# PERfECT-PRO2.net
KiCad netlist of a schematic drawn in Altium Designer
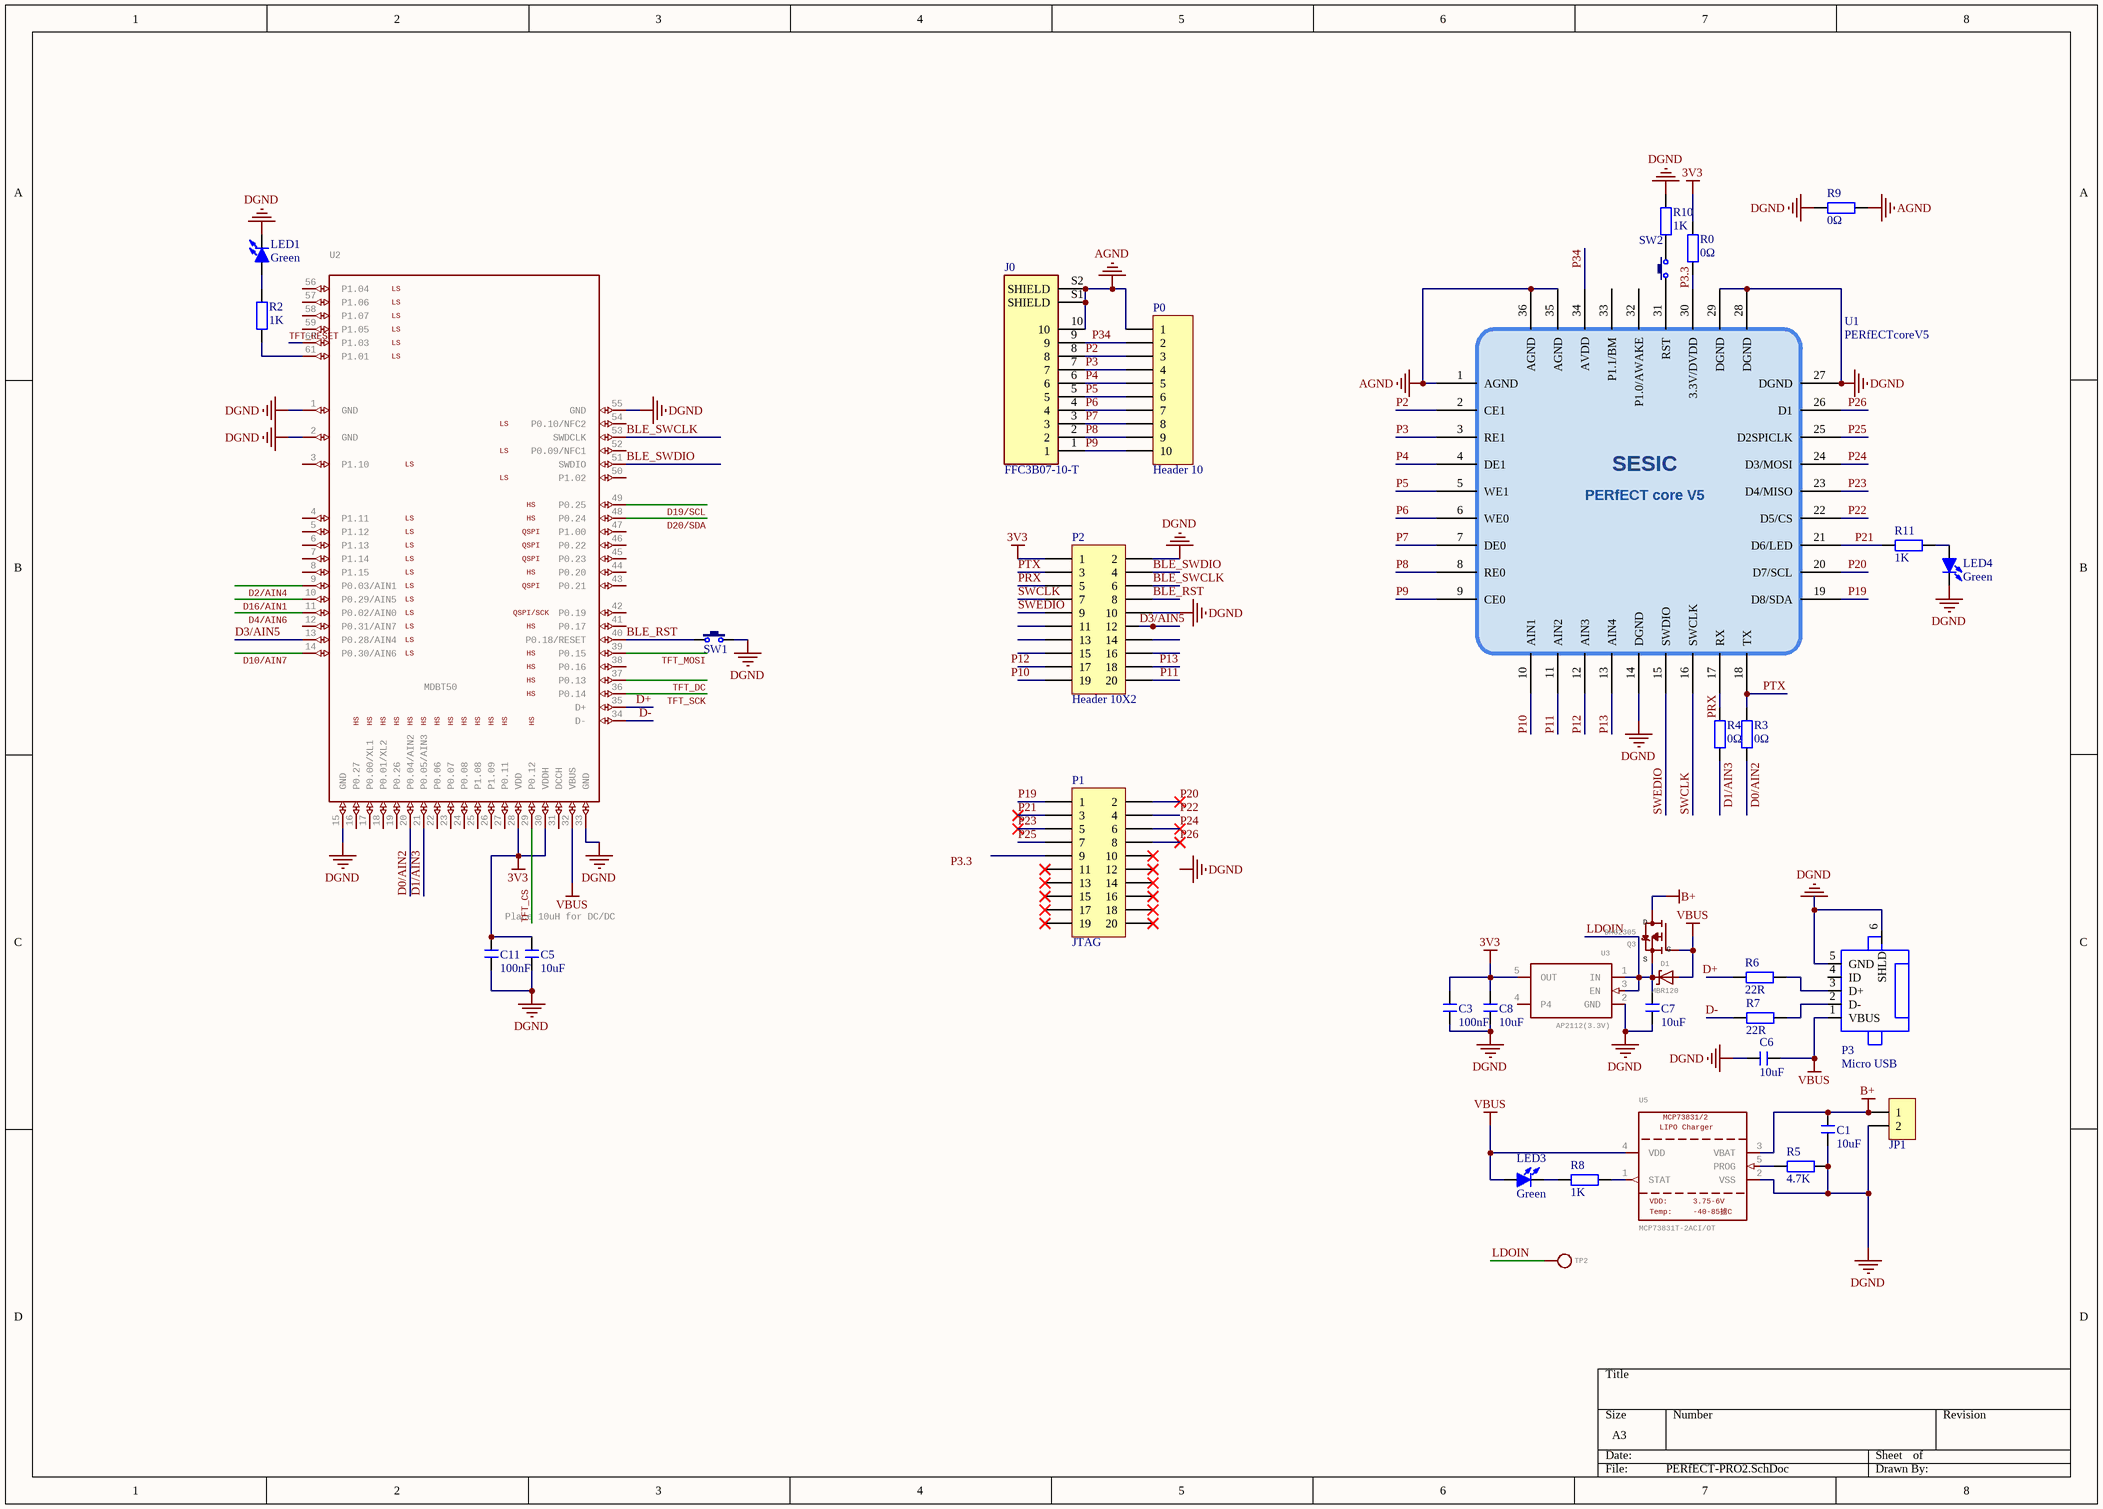
[diagram p0: PERfECT-PRO2.SchDoc]

(export (version "E")
  (design (tool "Eeschema 10.0.6"))
  (components
    (comp (ref "C1")
      (value "10uF")
      (footprint "LC-0603_C")
      (description "无极性贴片电容")
      (fields (field (name "版权归属") "源创客"))
      (libsource (lib "3.1   - 电阻-电容-电感") (part "C"))
    )
    (comp (ref "C3")
      (value "100nF")
      (footprint "LC-0603_C")
      (description "无极性贴片电容")
      (fields (field (name "版权归属") "源创客"))
      (libsource (lib "3.1   - 电阻-电容-电感") (part "C"))
    )
    (comp (ref "C5")
      (value "10uF")
      (footprint "LC-0603_C")
      (description "无极性贴片电容")
      (fields (field (name "版权归属") "源创客"))
      (libsource (lib "3.1   - 电阻-电容-电感") (part "C"))
    )
    (comp (ref "C6")
      (value "10uF")
      (footprint "LC-0603_C")
      (description "无极性贴片电容")
      (fields (field (name "版权归属") "源创客"))
      (libsource (lib "3.1   - 电阻-电容-电感") (part "C"))
    )
    (comp (ref "C7")
      (value "10uF")
      (footprint "LC-0603_C")
      (description "无极性贴片电容")
      (fields (field (name "版权归属") "源创客"))
      (libsource (lib "3.1   - 电阻-电容-电感") (part "C"))
    )
    (comp (ref "C8")
      (value "10uF")
      (footprint "LC-0603_C")
      (description "无极性贴片电容")
      (fields (field (name "版权归属") "源创客"))
      (libsource (lib "3.1   - 电阻-电容-电感") (part "C"))
    )
    (comp (ref "C11")
      (value "100nF")
      (footprint "LC-0603_C")
      (description "无极性贴片电容")
      (fields (field (name "版权归属") "源创客"))
      (libsource (lib "3.1   - 电阻-电容-电感") (part "C"))
    )
    (comp (ref "D1")
      (value "MBR120")
      (footprint "LC-SOD-123")
      (libsource (lib "microbuilder") (part "DIODE-SCHOTTKYSOD-123"))
    )
    (comp (ref "J0")
      (value "FFC3B07-10-T")
      (footprint "GCT_FFC3B07-10-T")
      (description "10 Position FFC, FPC Connector Contacts, Bottom 0.039 (1.00mm) Surface Mount, Right Angle")
      (fields (field (name "MF") "Global Connector Technology"))
      (libsource (lib "FFC3B07-10-T") (part "FFC3B07-10-T"))
    )
    (comp (ref "JP1")
      (value "HDR-1X2")
      (footprint "XH2.54-LI-2P")
      (description "2P接插件")
      (fields (field (name "版权归属") "源创客"))
      (libsource (lib "4.5   - 接插件-脚距2.54") (part "Header 2"))
    )
    (comp (ref "LED1")
      (value "Green")
      (footprint "LC-0603_LED_S1")
      (description "贴片LED")
      (fields (field (name "版权归属") "源创客"))
      (libsource (lib "9.1   - LED") (part "LED-SMD"))
    )
    (comp (ref "LED3")
      (value "Green")
      (footprint "0603_LED_S1")
      (description "贴片LED")
      (fields (field (name "版权归属") "源创客"))
      (libsource (lib "9.1   - LED") (part "LED-SMD"))
    )
    (comp (ref "LED4")
      (value "Green")
      (footprint "LC-0603_LED_S1")
      (description "贴片LED")
      (fields (field (name "版权归属") "源创客"))
      (libsource (lib "9.1   - LED") (part "LED-SMD"))
    )
    (comp (ref "P0")
      (value "Header 10")
      (footprint "HDR1X10")
      (description "Header, 10-Pin")
      (fields (field (name "PUBLISHER") "Altium Limited"))
      (libsource (lib "Miscellaneous Connectors") (part "Header 10"))
    )
    (comp (ref "P1")
      (value "JTAG")
      (footprint "HDR2X10")
      (description "Header, 10-Pin, Dual row")
      (fields (field (name "PUBLISHER") "Altium Limited"))
      (libsource (lib "PERfECT-PRO") (part "Header 10X2"))
    )
    (comp (ref "P2")
      (value "Header 10X2")
      (footprint "HDR2X10")
      (description "Header, 10-Pin, Dual row")
      (fields (field (name "PUBLISHER") "Altium Limited"))
      (libsource (lib "PERfECT-PRO") (part "Header 10X2"))
    )
    (comp (ref "P3")
      (value "Micro USB")
      (footprint "1981584-1")
      (description "CONN RCPT MICRO USB TYPE AB")
      (fields (field (name "MANUFACTURER") "REG CON") (field (name "PARTNUMBER") "C21377"))
      (libsource (lib "ESP32D") (part "1981584-1"))
    )
    (comp (ref "Q3")
      (value "DMG2305")
      (footprint "LC-SOT-23-3L")
      (fields (field (name "D") "D") (field (name "S") "S") (field (name "G") "G"))
      (libsource (lib "microbuilder") (part "MOSFET-P"))
    )
    (comp (ref "R0")
      (value "0Ω")
      (footprint "LC-0603_R")
      (description "贴片电阻")
      (fields (field (name "版权归属") "源创客"))
      (libsource (lib "3.1   - 电阻-电容-电感") (part "R"))
    )
    (comp (ref "R2")
      (value "1K")
      (footprint "LC-0603_R")
      (description "贴片电阻")
      (fields (field (name "版权归属") "源创客"))
      (libsource (lib "3.1   - 电阻-电容-电感") (part "R"))
    )
    (comp (ref "R3")
      (value "0Ω")
      (footprint "0603_R")
      (description "贴片电阻")
      (fields (field (name "版权归属") "源创客"))
      (libsource (lib "3.1   - 电阻-电容-电感") (part "R"))
    )
    (comp (ref "R4")
      (value "0Ω")
      (footprint "0603_R")
      (description "贴片电阻")
      (fields (field (name "版权归属") "源创客"))
      (libsource (lib "3.1   - 电阻-电容-电感") (part "R"))
    )
    (comp (ref "R5")
      (value "4.7K")
      (footprint "LC-0603_R")
      (description "贴片电阻")
      (fields (field (name "版权归属") "源创客"))
      (libsource (lib "3.1   - 电阻-电容-电感") (part "R"))
    )
    (comp (ref "R6")
      (value "22R")
      (footprint "LC-0603_R")
      (description "贴片电阻")
      (fields (field (name "版权归属") "源创客"))
      (libsource (lib "3.1   - 电阻-电容-电感") (part "R"))
    )
    (comp (ref "R7")
      (value "22R")
      (footprint "LC-0603_R")
      (description "贴片电阻")
      (fields (field (name "版权归属") "源创客"))
      (libsource (lib "3.1   - 电阻-电容-电感") (part "R"))
    )
    (comp (ref "R8")
      (value "1K")
      (footprint "0603_R")
      (description "贴片电阻")
      (fields (field (name "版权归属") "源创客"))
      (libsource (lib "3.1   - 电阻-电容-电感") (part "R"))
    )
    (comp (ref "R9")
      (value "0Ω")
      (footprint "LC-0603_R")
      (description "贴片电阻")
      (fields (field (name "版权归属") "源创客"))
      (libsource (lib "3.1   - 电阻-电容-电感") (part "R"))
    )
    (comp (ref "R10")
      (value "1K")
      (footprint "LC-0603_R")
      (description "贴片电阻")
      (fields (field (name "版权归属") "源创客"))
      (libsource (lib "3.1   - 电阻-电容-电感") (part "R"))
    )
    (comp (ref "R11")
      (value "1K")
      (footprint "LC-0603_R")
      (description "贴片电阻")
      (fields (field (name "版权归属") "源创客"))
      (libsource (lib "3.1   - 电阻-电容-电感") (part "R"))
    )
    (comp (ref "SW1")
      (value "3x6x5")
      (footprint "TSW SMD-3*6*2.5")
      (description "3x6轻触开关")
      (fields (field (name "版权归属") "源创客"))
      (libsource (lib "") (part "TSW 3x6_1"))
    )
    (comp (ref "SW2")
      (value "3x6x5")
      (footprint "TSW SMD-3*6*2.5")
      (description "3x6轻触开关")
      (fields (field (name "版权归属") "源创客"))
      (libsource (lib "5.1   - 按键-开关") (part "TSW 3x6"))
    )
    (comp (ref "TP2")
      (value "TESTPOINTROUND1.5MM")
      (footprint "TESTPOINT_ROUND_1.5MM")
      (libsource (lib "microbuilder") (part "TESTPOINTROUND1.5MM"))
    )
    (comp (ref "U1")
      (value "PERfECTcoreV5")
      (footprint "PERfECTcore36")
      (description "This is the 5th version of PERfEC core.https://github.com/WISE-PERfECT/PERfECT")
      (libsource (lib "PERfECT-PRO") (part "PERfECTcoreV5"))
    )
    (comp (ref "U2")
      (value "MDBT50")
      (footprint "MDBT50")
      (fields
        (field (name "LS") "LS")
        (field (name "LS_1") "LS")
        (field (name "LS_2") "LS")
        (field (name "LS_3") "LS")
        (field (name "LS_4") "LS")
        (field (name "LS_5") "LS")
        (field (name "LS_6") "LS")
        (field (name "LS_7") "LS")
        (field (name "LS_8") "LS")
        (field (name "HS") "HS")
        (field (name "HS_1") "HS")
        (field (name "HS_2") "HS")
        (field (name "HS_3") "HS")
        (field (name "HS_4") "HS")
        (field (name "HS_5") "HS")
        (field (name "HS_6") "HS")
        (field (name "HS_7") "HS")
        (field (name "HS_8") "HS")
        (field (name "QSPI") "QSPI")
        (field (name "QSPI_1") "QSPI")
        (field (name "QSPI_2") "QSPI")
        (field (name "QSPI_3") "QSPI")
        (field (name "QSPI/SCK") "QSPI/SCK")
      )
      (libsource (lib "microbuilder") (part "MDBT50"))
    )
    (comp (ref "U3")
      (value "AP2112(3.3V)")
      (footprint "Probe-Scope v1.0:SOT23-5")
      (libsource (lib "microbuilder") (part "VREG_SOT23-5"))
    )
    (comp (ref "U5")
      (value "MCP73831T-2ACI/OT")
      (footprint "SOT23-5")
      (fields
        (field (name "MCP73831/2") "MCP73831/2")
        (field (name "LIPOCHARGER") "LIPO Charger")
        (field (name "TEMP") "Temp:")
        (field (name "-40-85掳C") "-40-85掳C")
        (field (name "VDD") "VDD:")
        (field (name "3.75-6V") "3.75-6V")
      )
      (libsource (lib "microbuilder") (part "MCP73831/2"))
    )
  )
  (nets
    (net (code "1") (name "/BLE_RST") (class "Default")
      (node (ref "P2") (pin "8") (pinfunction "8_8") (pintype "passive"))
      (node (ref "SW1") (pin "1") (pinfunction "1_1") (pintype "passive"))
      (node (ref "U2") (pin "40") (pinfunction "P0.18/RESET_40") (pintype "bidirectional"))
    )
    (net (code "2") (name "/BLE_SWCLK") (class "Default")
      (node (ref "P2") (pin "6") (pinfunction "6_6") (pintype "passive"))
      (node (ref "U2") (pin "53") (pinfunction "SWDCLK_53") (pintype "bidirectional"))
    )
    (net (code "3") (name "/BLE_SWDIO") (class "Default")
      (node (ref "P2") (pin "4") (pinfunction "4_4") (pintype "passive"))
      (node (ref "U2") (pin "51") (pinfunction "SWDIO_51") (pintype "bidirectional"))
    )
    (net (code "4") (name "/D+") (class "Default")
      (node (ref "R6") (pin "1") (pinfunction "1_1") (pintype "passive"))
      (node (ref "U2") (pin "35") (pinfunction "D+_35") (pintype "bidirectional"))
    )
    (net (code "5") (name "/D-") (class "Default")
      (node (ref "R7") (pin "1") (pinfunction "1_1") (pintype "passive"))
      (node (ref "U2") (pin "34") (pinfunction "D-_34") (pintype "bidirectional"))
    )
    (net (code "6") (name "/D0{slash}AIN2") (class "Default")
      (node (ref "R3") (pin "2") (pinfunction "2_2") (pintype "passive"))
      (node (ref "U2") (pin "20") (pinfunction "P0.04/AIN2_20") (pintype "bidirectional"))
    )
    (net (code "7") (name "/D1{slash}AIN3") (class "Default")
      (node (ref "R4") (pin "2") (pinfunction "2_2") (pintype "passive"))
      (node (ref "U2") (pin "21") (pinfunction "P0.05/AIN3_21") (pintype "bidirectional"))
    )
    (net (code "8") (name "/D2{slash}AIN4") (class "Default")
      (node (ref "U2") (pin "9") (pinfunction "P0.03/AIN1_9") (pintype "bidirectional"))
    )
    (net (code "9") (name "/D3{slash}AIN5") (class "Default")
      (node (ref "P2") (pin "12") (pinfunction "12_12") (pintype "passive"))
      (node (ref "U2") (pin "13") (pinfunction "P0.28/AIN4_13") (pintype "bidirectional"))
    )
    (net (code "10") (name "/D4{slash}AIN6") (class "Default")
      (node (ref "U2") (pin "11") (pinfunction "P0.02/AIN0_11") (pintype "bidirectional"))
    )
    (net (code "11") (name "/D10{slash}AIN7") (class "Default")
      (node (ref "U2") (pin "14") (pinfunction "P0.30/AIN6_14") (pintype "bidirectional"))
    )
    (net (code "12") (name "/D16{slash}AIN1") (class "Default")
      (node (ref "U2") (pin "10") (pinfunction "P0.29/AIN5_10") (pintype "bidirectional"))
    )
    (net (code "13") (name "/D19{slash}SCL") (class "Default")
      (node (ref "U2") (pin "49") (pinfunction "P0.25_49") (pintype "bidirectional"))
    )
    (net (code "14") (name "/D20{slash}SDA") (class "Default")
      (node (ref "U2") (pin "48") (pinfunction "P0.24_48") (pintype "bidirectional"))
    )
    (net (code "15") (name "/LDOIN") (class "Default")
      (node (ref "C7") (pin "2") (pinfunction "2_2") (pintype "passive"))
      (node (ref "D1") (pin "C") (pinfunction "C_C") (pintype "passive"))
      (node (ref "Q3") (pin "2") (pinfunction "S_2") (pintype "passive"))
      (node (ref "TP2") (pin "P$1") (pinfunction "P$1_P$1") (pintype "bidirectional"))
      (node (ref "U3") (pin "1") (pinfunction "IN_1") (pintype "power_in"))
      (node (ref "U3") (pin "3") (pinfunction "EN_3") (pintype "input"))
    )
    (net (code "16") (name "/P2") (class "Default")
      (node (ref "J0") (pin "8") (pinfunction "8_8") (pintype "passive"))
      (node (ref "P0") (pin "3") (pinfunction "3_3") (pintype "passive"))
      (node (ref "U1") (pin "2") (pinfunction "CE1_2") (pintype "passive"))
    )
    (net (code "17") (name "/P3") (class "Default")
      (node (ref "J0") (pin "7") (pinfunction "7_7") (pintype "passive"))
      (node (ref "P0") (pin "4") (pinfunction "4_4") (pintype "passive"))
      (node (ref "U1") (pin "3") (pinfunction "RE1_3") (pintype "passive"))
    )
    (net (code "18") (name "/P3.3") (class "Default")
      (node (ref "R0") (pin "2") (pinfunction "2_2") (pintype "passive"))
      (node (ref "U1") (pin "30") (pinfunction "3.3V/DVDD_30") (pintype "passive"))
    )
    (net (code "19") (name "/P4") (class "Default")
      (node (ref "J0") (pin "6") (pinfunction "6_6") (pintype "passive"))
      (node (ref "P0") (pin "5") (pinfunction "5_5") (pintype "passive"))
      (node (ref "U1") (pin "4") (pinfunction "DE1_4") (pintype "passive"))
    )
    (net (code "20") (name "/P5") (class "Default")
      (node (ref "J0") (pin "5") (pinfunction "5_5") (pintype "passive"))
      (node (ref "P0") (pin "6") (pinfunction "6_6") (pintype "passive"))
      (node (ref "U1") (pin "5") (pinfunction "WE1_5") (pintype "passive"))
    )
    (net (code "21") (name "/P6") (class "Default")
      (node (ref "J0") (pin "4") (pinfunction "4_4") (pintype "passive"))
      (node (ref "P0") (pin "7") (pinfunction "7_7") (pintype "passive"))
      (node (ref "U1") (pin "6") (pinfunction "WE0_6") (pintype "passive"))
    )
    (net (code "22") (name "/P7") (class "Default")
      (node (ref "J0") (pin "3") (pinfunction "3_3") (pintype "passive"))
      (node (ref "P0") (pin "8") (pinfunction "8_8") (pintype "passive"))
      (node (ref "U1") (pin "7") (pinfunction "DE0_7") (pintype "passive"))
    )
    (net (code "23") (name "/P8") (class "Default")
      (node (ref "J0") (pin "2") (pinfunction "2_2") (pintype "passive"))
      (node (ref "P0") (pin "9") (pinfunction "9_9") (pintype "passive"))
      (node (ref "U1") (pin "8") (pinfunction "RE0_8") (pintype "passive"))
    )
    (net (code "24") (name "/P9") (class "Default")
      (node (ref "J0") (pin "1") (pinfunction "1_1") (pintype "passive"))
      (node (ref "P0") (pin "10") (pinfunction "10_10") (pintype "passive"))
      (node (ref "U1") (pin "9") (pinfunction "CE0_9") (pintype "passive"))
    )
    (net (code "25") (name "/P10") (class "Default")
      (node (ref "P2") (pin "19") (pinfunction "19_19") (pintype "passive"))
      (node (ref "U1") (pin "10") (pinfunction "AIN1_10") (pintype "passive"))
    )
    (net (code "26") (name "/P11") (class "Default")
      (node (ref "P2") (pin "20") (pinfunction "20_20") (pintype "passive"))
      (node (ref "U1") (pin "11") (pinfunction "AIN2_11") (pintype "passive"))
    )
    (net (code "27") (name "/P12") (class "Default")
      (node (ref "P2") (pin "17") (pinfunction "17_17") (pintype "passive"))
      (node (ref "U1") (pin "12") (pinfunction "AIN3_12") (pintype "passive"))
    )
    (net (code "28") (name "/P13") (class "Default")
      (node (ref "P2") (pin "18") (pinfunction "18_18") (pintype "passive"))
      (node (ref "U1") (pin "13") (pinfunction "AIN4_13") (pintype "passive"))
    )
    (net (code "29") (name "/P19") (class "Default")
      (node (ref "P1") (pin "1") (pinfunction "1_1") (pintype "passive"))
      (node (ref "U1") (pin "19") (pinfunction "D8/SDA_19") (pintype "passive"))
    )
    (net (code "30") (name "/P20") (class "Default")
      (node (ref "P1") (pin "2") (pinfunction "2_2") (pintype "passive"))
      (node (ref "U1") (pin "20") (pinfunction "D7/SCL_20") (pintype "passive"))
    )
    (net (code "31") (name "/P21") (class "Default")
      (node (ref "P1") (pin "3") (pinfunction "3_3") (pintype "passive"))
      (node (ref "R11") (pin "1") (pinfunction "1_1") (pintype "passive"))
      (node (ref "U1") (pin "21") (pinfunction "D6/LED_21") (pintype "passive"))
    )
    (net (code "32") (name "/P22") (class "Default")
      (node (ref "P1") (pin "4") (pinfunction "4_4") (pintype "passive"))
      (node (ref "U1") (pin "22") (pinfunction "D5/CS_22") (pintype "passive"))
    )
    (net (code "33") (name "/P23") (class "Default")
      (node (ref "P1") (pin "5") (pinfunction "5_5") (pintype "passive"))
      (node (ref "U1") (pin "23") (pinfunction "D4/MISO_23") (pintype "passive"))
    )
    (net (code "34") (name "/P24") (class "Default")
      (node (ref "P1") (pin "6") (pinfunction "6_6") (pintype "passive"))
      (node (ref "U1") (pin "24") (pinfunction "D3/MOSI_24") (pintype "passive"))
    )
    (net (code "35") (name "/P25") (class "Default")
      (node (ref "P1") (pin "7") (pinfunction "7_7") (pintype "passive"))
      (node (ref "U1") (pin "25") (pinfunction "D2SPICLK_25") (pintype "passive"))
    )
    (net (code "36") (name "/P26") (class "Default")
      (node (ref "P1") (pin "8") (pinfunction "8_8") (pintype "passive"))
      (node (ref "U1") (pin "26") (pinfunction "D1_26") (pintype "passive"))
    )
    (net (code "37") (name "/P34") (class "Default")
      (node (ref "J0") (pin "9") (pinfunction "9_9") (pintype "passive"))
      (node (ref "P0") (pin "2") (pinfunction "2_2") (pintype "passive"))
      (node (ref "U1") (pin "34") (pinfunction "AVDD_34") (pintype "passive"))
    )
    (net (code "38") (name "/PRX") (class "Default")
      (node (ref "P2") (pin "5") (pinfunction "5_5") (pintype "passive"))
      (node (ref "R4") (pin "1") (pinfunction "1_1") (pintype "passive"))
      (node (ref "U1") (pin "17") (pinfunction "RX_17") (pintype "passive"))
    )
    (net (code "39") (name "/PTX") (class "Default")
      (node (ref "P2") (pin "3") (pinfunction "3_3") (pintype "passive"))
      (node (ref "R3") (pin "1") (pinfunction "1_1") (pintype "passive"))
      (node (ref "U1") (pin "18") (pinfunction "TX_18") (pintype "passive"))
    )
    (net (code "40") (name "/SWCLK") (class "Default")
      (node (ref "P2") (pin "7") (pinfunction "7_7") (pintype "passive"))
      (node (ref "U1") (pin "16") (pinfunction "SWCLK_16") (pintype "passive"))
    )
    (net (code "41") (name "/SWEDIO") (class "Default")
      (node (ref "P2") (pin "9") (pinfunction "9_9") (pintype "passive"))
      (node (ref "U1") (pin "15") (pinfunction "SWDIO_15") (pintype "passive"))
    )
    (net (code "42") (name "/TFT_CS") (class "Default")
      (node (ref "U2") (pin "29") (pinfunction "P0.12_29") (pintype "bidirectional"))
    )
    (net (code "43") (name "/TFT_DC") (class "Default")
      (node (ref "U2") (pin "37") (pinfunction "P0.13_37") (pintype "bidirectional"))
    )
    (net (code "44") (name "/TFT_MOSI") (class "Default")
      (node (ref "U2") (pin "39") (pinfunction "P0.15_39") (pintype "bidirectional"))
    )
    (net (code "45") (name "/TFT_RESET") (class "Default")
      (node (ref "U2") (pin "60") (pinfunction "P1.03_60") (pintype "bidirectional"))
    )
    (net (code "46") (name "/TFT_SCK") (class "Default")
      (node (ref "U2") (pin "36") (pinfunction "P0.14_36") (pintype "bidirectional"))
    )
    (net (code "47") (name "3V3") (class "Default")
      (node (ref "C11") (pin "2") (pinfunction "2_2") (pintype "passive"))
      (node (ref "C3") (pin "2") (pinfunction "2_2") (pintype "passive"))
      (node (ref "C5") (pin "2") (pinfunction "2_2") (pintype "passive"))
      (node (ref "C8") (pin "2") (pinfunction "2_2") (pintype "passive"))
      (node (ref "P2") (pin "1") (pinfunction "1_1") (pintype "passive"))
      (node (ref "R0") (pin "1") (pinfunction "1_1") (pintype "passive"))
      (node (ref "U2") (pin "28") (pinfunction "VDD_28") (pintype "bidirectional"))
      (node (ref "U2") (pin "30") (pinfunction "VDDH_30") (pintype "bidirectional"))
      (node (ref "U3") (pin "5") (pinfunction "OUT_5") (pintype "power_in"))
    )
    (net (code "48") (name "AGND") (class "Default")
      (node (ref "J0") (pin "10") (pinfunction "10_10") (pintype "passive"))
      (node (ref "J0") (pin "S1") (pinfunction "SHIELD_S1") (pintype "passive"))
      (node (ref "J0") (pin "S2") (pinfunction "SHIELD_S2") (pintype "passive"))
      (node (ref "P0") (pin "1") (pinfunction "1_1") (pintype "passive"))
      (node (ref "R9") (pin "2") (pinfunction "2_2") (pintype "passive"))
      (node (ref "U1") (pin "1") (pinfunction "AGND_1") (pintype "passive"))
      (node (ref "U1") (pin "35") (pinfunction "AGND_35") (pintype "passive"))
      (node (ref "U1") (pin "36") (pinfunction "AGND_36") (pintype "passive"))
    )
    (net (code "49") (name "B+") (class "Default")
      (node (ref "C1") (pin "2") (pinfunction "2_2") (pintype "passive"))
      (node (ref "JP1") (pin "1") (pinfunction "1_1") (pintype "passive"))
      (node (ref "Q3") (pin "3") (pinfunction "D_3") (pintype "passive"))
      (node (ref "U5") (pin "3") (pinfunction "VBAT_3") (pintype "power_in"))
    )
    (net (code "50") (name "DGND") (class "Default")
      (node (ref "C1") (pin "1") (pinfunction "1_1") (pintype "passive"))
      (node (ref "C11") (pin "1") (pinfunction "1_1") (pintype "passive"))
      (node (ref "C3") (pin "1") (pinfunction "1_1") (pintype "passive"))
      (node (ref "C5") (pin "1") (pinfunction "1_1") (pintype "passive"))
      (node (ref "C6") (pin "2") (pinfunction "2_2") (pintype "passive"))
      (node (ref "C7") (pin "1") (pinfunction "1_1") (pintype "passive"))
      (node (ref "C8") (pin "1") (pinfunction "1_1") (pintype "passive"))
      (node (ref "JP1") (pin "2") (pinfunction "2_2") (pintype "passive"))
      (node (ref "LED1") (pin "2") (pinfunction "K_2") (pintype "passive"))
      (node (ref "LED4") (pin "2") (pinfunction "K_2") (pintype "passive"))
      (node (ref "P2") (pin "10") (pinfunction "10_10") (pintype "passive"))
      (node (ref "P2") (pin "2") (pinfunction "2_2") (pintype "passive"))
      (node (ref "P3") (pin "5") (pinfunction "GND_5") (pintype "power_in"))
      (node (ref "P3") (pin "6") (pinfunction "SHLD_6") (pintype "power_in"))
      (node (ref "R10") (pin "2") (pinfunction "2_2") (pintype "passive"))
      (node (ref "R5") (pin "2") (pinfunction "2_2") (pintype "passive"))
      (node (ref "R9") (pin "1") (pinfunction "1_1") (pintype "passive"))
      (node (ref "SW1") (pin "2") (pinfunction "2_2") (pintype "passive"))
      (node (ref "U1") (pin "14") (pinfunction "DGND_14") (pintype "passive"))
      (node (ref "U1") (pin "27") (pinfunction "DGND_27") (pintype "passive"))
      (node (ref "U1") (pin "28") (pinfunction "DGND_28") (pintype "power_in"))
      (node (ref "U1") (pin "29") (pinfunction "DGND_29") (pintype "passive"))
      (node (ref "U2") (pin "1") (pinfunction "GND_1") (pintype "bidirectional"))
      (node (ref "U2") (pin "15") (pinfunction "GND_15") (pintype "bidirectional"))
      (node (ref "U2") (pin "2") (pinfunction "GND_2") (pintype "bidirectional"))
      (node (ref "U2") (pin "33") (pinfunction "GND_33") (pintype "bidirectional"))
      (node (ref "U2") (pin "55") (pinfunction "GND_55") (pintype "bidirectional"))
      (node (ref "U3") (pin "2") (pinfunction "GND_2") (pintype "power_in"))
      (node (ref "U5") (pin "2") (pinfunction "VSS_2") (pintype "power_in"))
    )
    (net (code "51") (name "Net-(LED1-A)") (class "Default")
      (node (ref "LED1") (pin "1") (pinfunction "A_1") (pintype "passive"))
      (node (ref "R2") (pin "2") (pinfunction "2_2") (pintype "passive"))
    )
    (net (code "52") (name "Net-(LED3-K)") (class "Default")
      (node (ref "LED3") (pin "2") (pinfunction "K_2") (pintype "passive"))
      (node (ref "R8") (pin "1") (pinfunction "1_1") (pintype "passive"))
    )
    (net (code "53") (name "Net-(LED4-A)") (class "Default")
      (node (ref "LED4") (pin "1") (pinfunction "A_1") (pintype "passive"))
      (node (ref "R11") (pin "2") (pinfunction "2_2") (pintype "passive"))
    )
    (net (code "54") (name "Net-(P3-D+)") (class "Default")
      (node (ref "P3") (pin "3") (pinfunction "D+_3") (pintype "passive"))
      (node (ref "R6") (pin "2") (pinfunction "2_2") (pintype "passive"))
    )
    (net (code "55") (name "Net-(P3-D-)") (class "Default")
      (node (ref "P3") (pin "2") (pinfunction "D-_2") (pintype "passive"))
      (node (ref "R7") (pin "2") (pinfunction "2_2") (pintype "passive"))
    )
    (net (code "56") (name "Net-(R10-Pad1)") (class "Default")
      (node (ref "R10") (pin "1") (pinfunction "1_1") (pintype "passive"))
      (node (ref "SW2") (pin "2") (pinfunction "2_2") (pintype "passive"))
    )
    (net (code "57") (name "Net-(U1-RST)") (class "Default")
      (node (ref "SW2") (pin "1") (pinfunction "1_1") (pintype "passive"))
      (node (ref "U1") (pin "31") (pinfunction "RST_31") (pintype "passive"))
    )
    (net (code "58") (name "Net-(U2-P1.01)") (class "Default")
      (node (ref "R2") (pin "1") (pinfunction "1_1") (pintype "passive"))
      (node (ref "U2") (pin "61") (pinfunction "P1.01_61") (pintype "bidirectional"))
    )
    (net (code "59") (name "Net-(U5-PROG)") (class "Default")
      (node (ref "R5") (pin "1") (pinfunction "1_1") (pintype "passive"))
      (node (ref "U5") (pin "5") (pinfunction "PROG_5") (pintype "input"))
    )
    (net (code "60") (name "Net-(U5-STAT)") (class "Default")
      (node (ref "R8") (pin "2") (pinfunction "2_2") (pintype "passive"))
      (node (ref "U5") (pin "1") (pinfunction "STAT_1") (pintype "output"))
    )
    (net (code "61") (name "VBUS") (class "Default")
      (node (ref "C6") (pin "1") (pinfunction "1_1") (pintype "passive"))
      (node (ref "D1") (pin "A") (pinfunction "A_A") (pintype "passive"))
      (node (ref "LED3") (pin "1") (pinfunction "A_1") (pintype "passive"))
      (node (ref "P3") (pin "1") (pinfunction "VBUS_1") (pintype "power_in"))
      (node (ref "Q3") (pin "1") (pinfunction "G_1") (pintype "passive"))
      (node (ref "U2") (pin "32") (pinfunction "VBUS_32") (pintype "bidirectional"))
      (node (ref "U5") (pin "4") (pinfunction "VDD_4") (pintype "power_in"))
    )
    (net (code "62") (name "unconnected-(P1-Pad9)") (class "Default")
      (node (ref "P1") (pin "9") (pinfunction "9_9") (pintype "passive"))
    )
    (net (code "63") (name "unconnected-(P1-Pad10)") (class "Default")
      (node (ref "P1") (pin "10") (pinfunction "10_10") (pintype "passive+no_connect"))
    )
    (net (code "64") (name "unconnected-(P1-Pad11)") (class "Default")
      (node (ref "P1") (pin "11") (pinfunction "11_11") (pintype "passive+no_connect"))
    )
    (net (code "65") (name "unconnected-(P1-Pad12)") (class "Default")
      (node (ref "P1") (pin "12") (pinfunction "12_12") (pintype "passive+no_connect"))
    )
    (net (code "66") (name "unconnected-(P1-Pad13)") (class "Default")
      (node (ref "P1") (pin "13") (pinfunction "13_13") (pintype "passive+no_connect"))
    )
    (net (code "67") (name "unconnected-(P1-Pad14)") (class "Default")
      (node (ref "P1") (pin "14") (pinfunction "14_14") (pintype "passive+no_connect"))
    )
    (net (code "68") (name "unconnected-(P1-Pad15)") (class "Default")
      (node (ref "P1") (pin "15") (pinfunction "15_15") (pintype "passive+no_connect"))
    )
    (net (code "69") (name "unconnected-(P1-Pad16)") (class "Default")
      (node (ref "P1") (pin "16") (pinfunction "16_16") (pintype "passive+no_connect"))
    )
    (net (code "70") (name "unconnected-(P1-Pad17)") (class "Default")
      (node (ref "P1") (pin "17") (pinfunction "17_17") (pintype "passive+no_connect"))
    )
    (net (code "71") (name "unconnected-(P1-Pad18)") (class "Default")
      (node (ref "P1") (pin "18") (pinfunction "18_18") (pintype "passive+no_connect"))
    )
    (net (code "72") (name "unconnected-(P1-Pad19)") (class "Default")
      (node (ref "P1") (pin "19") (pinfunction "19_19") (pintype "passive+no_connect"))
    )
    (net (code "73") (name "unconnected-(P1-Pad20)") (class "Default")
      (node (ref "P1") (pin "20") (pinfunction "20_20") (pintype "passive+no_connect"))
    )
    (net (code "74") (name "unconnected-(P2-Pad11)") (class "Default")
      (node (ref "P2") (pin "11") (pinfunction "11_11") (pintype "passive"))
    )
    (net (code "75") (name "unconnected-(P2-Pad13)") (class "Default")
      (node (ref "P2") (pin "13") (pinfunction "13_13") (pintype "passive"))
    )
    (net (code "76") (name "unconnected-(P2-Pad14)") (class "Default")
      (node (ref "P2") (pin "14") (pinfunction "14_14") (pintype "passive"))
    )
    (net (code "77") (name "unconnected-(P2-Pad15)") (class "Default")
      (node (ref "P2") (pin "15") (pinfunction "15_15") (pintype "passive"))
    )
    (net (code "78") (name "unconnected-(P2-Pad16)") (class "Default")
      (node (ref "P2") (pin "16") (pinfunction "16_16") (pintype "passive"))
    )
    (net (code "79") (name "unconnected-(P3-ID-Pad4)") (class "Default")
      (node (ref "P3") (pin "4") (pinfunction "ID_4") (pintype "passive"))
    )
    (net (code "80") (name "unconnected-(U1-P1.0{slash}AWAKE-Pad32)") (class "Default")
      (node (ref "U1") (pin "32") (pinfunction "P1.0/AWAKE_32") (pintype "passive"))
    )
    (net (code "81") (name "unconnected-(U1-P1.1{slash}BM-Pad33)") (class "Default")
      (node (ref "U1") (pin "33") (pinfunction "P1.1/BM_33") (pintype "passive"))
    )
    (net (code "82") (name "unconnected-(U2-DCCH-Pad31)") (class "Default")
      (node (ref "U2") (pin "31") (pinfunction "DCCH_31") (pintype "bidirectional"))
    )
    (net (code "83") (name "unconnected-(U2-P0.00{slash}XL1-Pad17)") (class "Default")
      (node (ref "U2") (pin "17") (pinfunction "P0.00/XL1_17") (pintype "bidirectional"))
    )
    (net (code "84") (name "unconnected-(U2-P0.01{slash}XL2-Pad18)") (class "Default")
      (node (ref "U2") (pin "18") (pinfunction "P0.01/XL2_18") (pintype "bidirectional"))
    )
    (net (code "85") (name "unconnected-(U2-P0.06-Pad22)") (class "Default")
      (node (ref "U2") (pin "22") (pinfunction "P0.06_22") (pintype "bidirectional"))
    )
    (net (code "86") (name "unconnected-(U2-P0.07-Pad23)") (class "Default")
      (node (ref "U2") (pin "23") (pinfunction "P0.07_23") (pintype "bidirectional"))
    )
    (net (code "87") (name "unconnected-(U2-P0.08-Pad24)") (class "Default")
      (node (ref "U2") (pin "24") (pinfunction "P0.08_24") (pintype "bidirectional"))
    )
    (net (code "88") (name "unconnected-(U2-P0.09{slash}NFC1-Pad52)") (class "Default")
      (node (ref "U2") (pin "52") (pinfunction "P0.09/NFC1_52") (pintype "bidirectional"))
    )
    (net (code "89") (name "unconnected-(U2-P0.10{slash}NFC2-Pad54)") (class "Default")
      (node (ref "U2") (pin "54") (pinfunction "P0.10/NFC2_54") (pintype "bidirectional"))
    )
    (net (code "90") (name "unconnected-(U2-P0.11-Pad27)") (class "Default")
      (node (ref "U2") (pin "27") (pinfunction "P0.11_27") (pintype "bidirectional"))
    )
    (net (code "91") (name "unconnected-(U2-P0.16-Pad38)") (class "Default")
      (node (ref "U2") (pin "38") (pinfunction "P0.16_38") (pintype "bidirectional"))
    )
    (net (code "92") (name "unconnected-(U2-P0.17-Pad41)") (class "Default")
      (node (ref "U2") (pin "41") (pinfunction "P0.17_41") (pintype "bidirectional"))
    )
    (net (code "93") (name "unconnected-(U2-P0.19-Pad42)") (class "Default")
      (node (ref "U2") (pin "42") (pinfunction "P0.19_42") (pintype "bidirectional"))
    )
    (net (code "94") (name "unconnected-(U2-P0.20-Pad44)") (class "Default")
      (node (ref "U2") (pin "44") (pinfunction "P0.20_44") (pintype "bidirectional"))
    )
    (net (code "95") (name "unconnected-(U2-P0.21-Pad43)") (class "Default")
      (node (ref "U2") (pin "43") (pinfunction "P0.21_43") (pintype "bidirectional"))
    )
    (net (code "96") (name "unconnected-(U2-P0.22-Pad46)") (class "Default")
      (node (ref "U2") (pin "46") (pinfunction "P0.22_46") (pintype "bidirectional"))
    )
    (net (code "97") (name "unconnected-(U2-P0.23-Pad45)") (class "Default")
      (node (ref "U2") (pin "45") (pinfunction "P0.23_45") (pintype "bidirectional"))
    )
    (net (code "98") (name "unconnected-(U2-P0.26-Pad19)") (class "Default")
      (node (ref "U2") (pin "19") (pinfunction "P0.26_19") (pintype "bidirectional"))
    )
    (net (code "99") (name "unconnected-(U2-P0.27-Pad16)") (class "Default")
      (node (ref "U2") (pin "16") (pinfunction "P0.27_16") (pintype "bidirectional"))
    )
    (net (code "100") (name "unconnected-(U2-P0.31{slash}AIN7-Pad12)") (class "Default")
      (node (ref "U2") (pin "12") (pinfunction "P0.31/AIN7_12") (pintype "bidirectional"))
    )
    (net (code "101") (name "unconnected-(U2-P1.00-Pad47)") (class "Default")
      (node (ref "U2") (pin "47") (pinfunction "P1.00_47") (pintype "bidirectional"))
    )
    (net (code "102") (name "unconnected-(U2-P1.02-Pad50)") (class "Default")
      (node (ref "U2") (pin "50") (pinfunction "P1.02_50") (pintype "bidirectional"))
    )
    (net (code "103") (name "unconnected-(U2-P1.04-Pad56)") (class "Default")
      (node (ref "U2") (pin "56") (pinfunction "P1.04_56") (pintype "bidirectional"))
    )
    (net (code "104") (name "unconnected-(U2-P1.05-Pad59)") (class "Default")
      (node (ref "U2") (pin "59") (pinfunction "P1.05_59") (pintype "bidirectional"))
    )
    (net (code "105") (name "unconnected-(U2-P1.06-Pad57)") (class "Default")
      (node (ref "U2") (pin "57") (pinfunction "P1.06_57") (pintype "bidirectional"))
    )
    (net (code "106") (name "unconnected-(U2-P1.07-Pad58)") (class "Default")
      (node (ref "U2") (pin "58") (pinfunction "P1.07_58") (pintype "bidirectional"))
    )
    (net (code "107") (name "unconnected-(U2-P1.08-Pad25)") (class "Default")
      (node (ref "U2") (pin "25") (pinfunction "P1.08_25") (pintype "bidirectional"))
    )
    (net (code "108") (name "unconnected-(U2-P1.09-Pad26)") (class "Default")
      (node (ref "U2") (pin "26") (pinfunction "P1.09_26") (pintype "bidirectional"))
    )
    (net (code "109") (name "unconnected-(U2-P1.10-Pad3)") (class "Default")
      (node (ref "U2") (pin "3") (pinfunction "P1.10_3") (pintype "bidirectional"))
    )
    (net (code "110") (name "unconnected-(U2-P1.11-Pad4)") (class "Default")
      (node (ref "U2") (pin "4") (pinfunction "P1.11_4") (pintype "bidirectional"))
    )
    (net (code "111") (name "unconnected-(U2-P1.12-Pad5)") (class "Default")
      (node (ref "U2") (pin "5") (pinfunction "P1.12_5") (pintype "bidirectional"))
    )
    (net (code "112") (name "unconnected-(U2-P1.13-Pad6)") (class "Default")
      (node (ref "U2") (pin "6") (pinfunction "P1.13_6") (pintype "bidirectional"))
    )
    (net (code "113") (name "unconnected-(U2-P1.14-Pad7)") (class "Default")
      (node (ref "U2") (pin "7") (pinfunction "P1.14_7") (pintype "bidirectional"))
    )
    (net (code "114") (name "unconnected-(U2-P1.15-Pad8)") (class "Default")
      (node (ref "U2") (pin "8") (pinfunction "P1.15_8") (pintype "bidirectional"))
    )
    (net (code "115") (name "unconnected-(U3-P4-Pad4)") (class "Default")
      (node (ref "U3") (pin "4") (pinfunction "P4_4") (pintype "bidirectional"))
    )
  )
)
